# SeptinaryAI_Balldi__elec_driver__driver_.net
KiCad netlist of a schematic drawn in Altium Designer
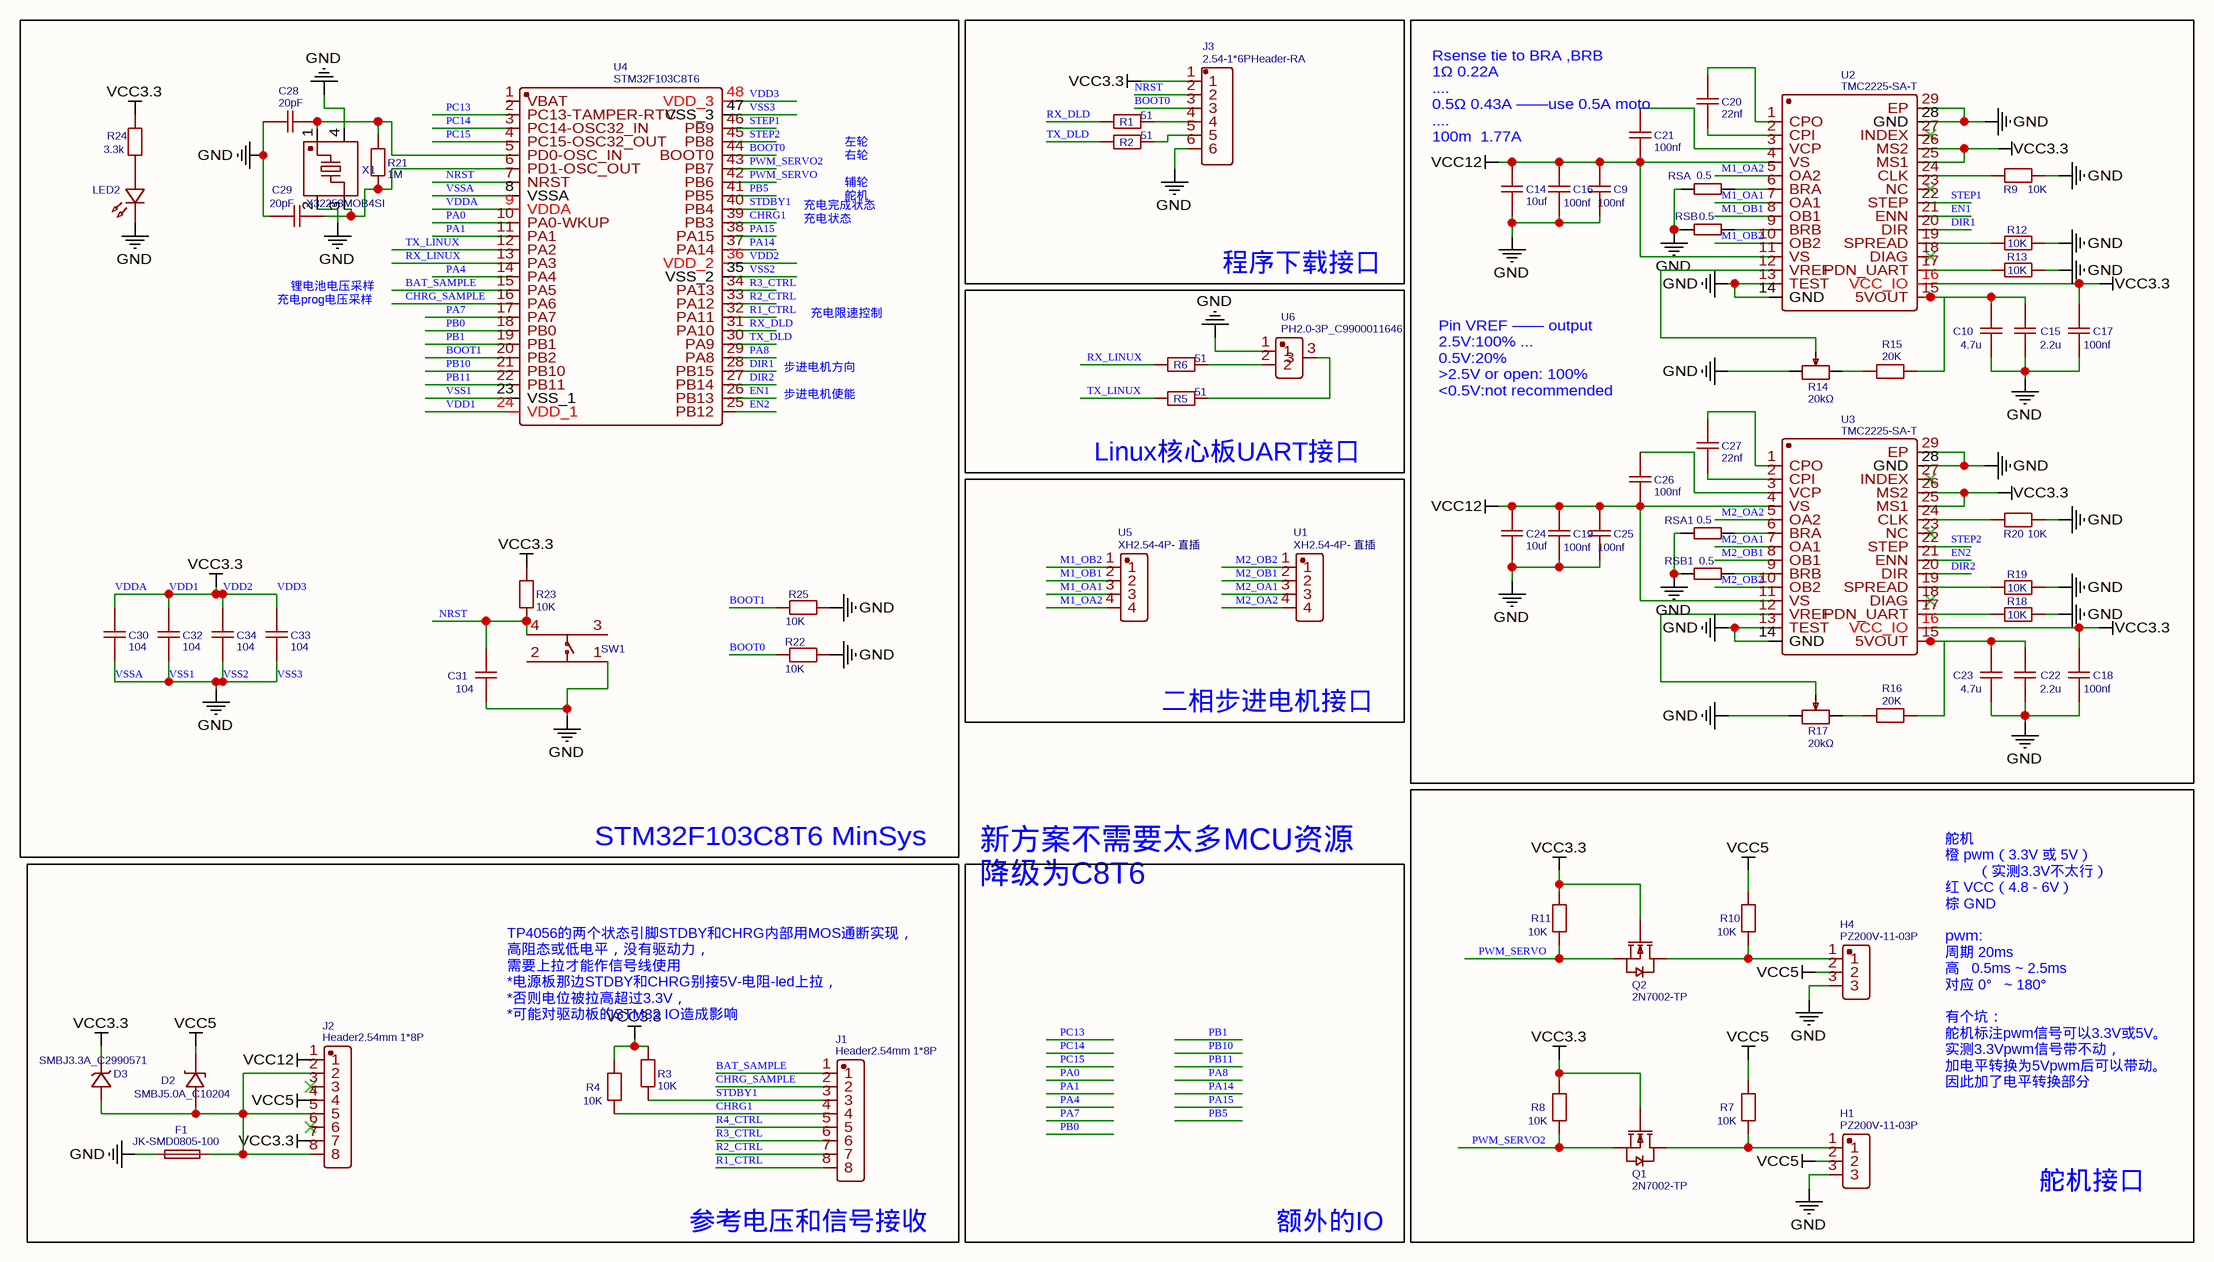
[diagram p0: SeptinaryAI_Balldi__elec_driver__driver_2023-07-21.schdoc]

(export (version "E")
  (design (tool "Eeschema 10.0.6"))
  (components
    (comp (ref "C9")
      (value "100nf")
      (fields (field (name "CONTRIBUTOR") "LCEDA_Lib"))
      (libsource (lib "altium-import") (part "root_1_100nf_"))
    )
    (comp (ref "C10")
      (value "4.7u")
      (fields (field (name "CONTRIBUTOR") "LCSC"))
      (libsource (lib "altium-import") (part "root_1_4.7u_"))
    )
    (comp (ref "C14")
      (value "10uf")
      (fields (field (name "CONTRIBUTOR") "LCEDA_Lib"))
      (libsource (lib "altium-import") (part "root_1_10uf_"))
    )
    (comp (ref "C15")
      (value "2.2u")
      (fields (field (name "CONTRIBUTOR") "LCSC"))
      (libsource (lib "altium-import") (part "root_1_2.2u_"))
    )
    (comp (ref "C16")
      (value "100nf")
      (fields (field (name "CONTRIBUTOR") "LCEDA_Lib"))
      (libsource (lib "altium-import") (part "root_1_100nf_"))
    )
    (comp (ref "C17")
      (value "100nf")
      (fields (field (name "CONTRIBUTOR") "LCEDA_Lib"))
      (libsource (lib "altium-import") (part "root_1_100nf_"))
    )
    (comp (ref "C18")
      (value "100nf")
      (fields (field (name "CONTRIBUTOR") "LCEDA_Lib"))
      (libsource (lib "altium-import") (part "root_1_100nf_"))
    )
    (comp (ref "C19")
      (value "100nf")
      (fields (field (name "CONTRIBUTOR") "LCEDA_Lib"))
      (libsource (lib "altium-import") (part "root_1_100nf_"))
    )
    (comp (ref "C20")
      (value "22nf")
      (fields (field (name "CONTRIBUTOR") "LCEDA_Lib"))
      (libsource (lib "altium-import") (part "root_1_22nf_"))
    )
    (comp (ref "C21")
      (value "100nf")
      (fields (field (name "CONTRIBUTOR") "LCEDA_Lib"))
      (libsource (lib "altium-import") (part "root_1_100nf_"))
    )
    (comp (ref "C22")
      (value "2.2u")
      (fields (field (name "CONTRIBUTOR") "LCSC"))
      (libsource (lib "altium-import") (part "root_1_2.2u_"))
    )
    (comp (ref "C23")
      (value "4.7u")
      (fields (field (name "CONTRIBUTOR") "LCSC"))
      (libsource (lib "altium-import") (part "root_1_4.7u_"))
    )
    (comp (ref "C24")
      (value "10uf")
      (fields (field (name "CONTRIBUTOR") "LCEDA_Lib"))
      (libsource (lib "altium-import") (part "root_1_10uf_"))
    )
    (comp (ref "C25")
      (value "100nf")
      (fields (field (name "CONTRIBUTOR") "LCEDA_Lib"))
      (libsource (lib "altium-import") (part "root_1_100nf_"))
    )
    (comp (ref "C26")
      (value "100nf")
      (fields (field (name "CONTRIBUTOR") "LCEDA_Lib"))
      (libsource (lib "altium-import") (part "root_1_100nf_"))
    )
    (comp (ref "C27")
      (value "22nf")
      (fields (field (name "CONTRIBUTOR") "LCEDA_Lib"))
      (libsource (lib "altium-import") (part "root_1_22nf_"))
    )
    (comp (ref "C28")
      (value "20pF")
      (fields (field (name "CONTRIBUTOR") "LCSC"))
      (libsource (lib "altium-import") (part "root_2_20pF_"))
    )
    (comp (ref "C29")
      (value "20pF")
      (fields (field (name "CONTRIBUTOR") "LCSC"))
      (libsource (lib "altium-import") (part "root_2_20pF_"))
    )
    (comp (ref "C30")
      (value "104")
      (fields (field (name "CONTRIBUTOR") "LCSC"))
      (libsource (lib "altium-import") (part "root_1_104_"))
    )
    (comp (ref "C31")
      (value "104")
      (fields (field (name "CONTRIBUTOR") "LCSC"))
      (libsource (lib "altium-import") (part "root_1_104_"))
    )
    (comp (ref "C32")
      (value "104")
      (fields (field (name "CONTRIBUTOR") "LCSC"))
      (libsource (lib "altium-import") (part "root_1_104_"))
    )
    (comp (ref "C33")
      (value "104")
      (fields (field (name "CONTRIBUTOR") "LCSC"))
      (libsource (lib "altium-import") (part "root_1_104_"))
    )
    (comp (ref "C34")
      (value "104")
      (fields (field (name "CONTRIBUTOR") "LCSC"))
      (libsource (lib "altium-import") (part "root_1_104_"))
    )
    (comp (ref "D2")
      (value "SMBJ5.0A_C10204")
      (libsource (lib "altium-import") (part "root_3_SMBJ5.0A_C10204_"))
    )
    (comp (ref "D3")
      (value "SMBJ3.3A_C2990571")
      (fields
        (field (name "BOM_SUPPLIER PART") "C2990571")
        (field (name "BOM_MANUFACTURER PART") "SMBJ3.3A")
        (field (name "CONTRIBUTOR") "lcsc")
      )
      (libsource (lib "altium-import") (part "root_3_SMBJ3.3A_C2990571_"))
    )
    (comp (ref "F1")
      (value "JK-SMD0805-100")
      (fields (field (name "CONTRIBUTOR") "LCSC"))
      (libsource (lib "altium-import") (part "root_0_JK-SMD0805-100_"))
    )
    (comp (ref "H1")
      (value "PZ200V-11-03P")
      (fields (field (name "CONTRIBUTOR") "LCSC"))
      (libsource (lib "altium-import") (part "root_0_PZ200V-11-03P_"))
    )
    (comp (ref "H4")
      (value "PZ200V-11-03P")
      (fields (field (name "CONTRIBUTOR") "LCSC"))
      (libsource (lib "altium-import") (part "root_0_PZ200V-11-03P_"))
    )
    (comp (ref "J1")
      (value "Header2.54mm 1*8P")
      (libsource (lib "altium-import") (part "root_0_Header2.54mm 1*8P_"))
    )
    (comp (ref "J2")
      (value "Header2.54mm 1*8P")
      (libsource (lib "altium-import") (part "root_0_Header2.54mm 1*8P_"))
    )
    (comp (ref "J3")
      (value "2.54-1*6PHeader-RA")
      (libsource (lib "altium-import") (part "root_0_2.54-1*6PHeader-RA_"))
    )
    (comp (ref "LED2")
      (value "LC191TBCT")
      (fields (field (name "CONTRIBUTOR") "LCSC"))
      (libsource (lib "altium-import") (part "root_1_LC191TBCT_"))
    )
    (comp (ref "Q1")
      (value "2N7002-TP")
      (fields (field (name "CONTRIBUTOR") "LCSC"))
      (libsource (lib "altium-import") (part "root_3_2N7002-TP_"))
    )
    (comp (ref "Q2")
      (value "2N7002-TP")
      (fields (field (name "CONTRIBUTOR") "LCSC"))
      (libsource (lib "altium-import") (part "root_3_2N7002-TP_"))
    )
    (comp (ref "R1")
      (value "51")
      (fields (field (name "CONTRIBUTOR") "LCSC"))
      (libsource (lib "altium-import") (part "root_0_51_"))
    )
    (comp (ref "R2")
      (value "51")
      (fields (field (name "CONTRIBUTOR") "LCSC"))
      (libsource (lib "altium-import") (part "root_0_51_"))
    )
    (comp (ref "R3")
      (value "10K")
      (fields (field (name "CONTRIBUTOR") "LCSC"))
      (libsource (lib "altium-import") (part "root_3_10K_"))
    )
    (comp (ref "R4")
      (value "10K")
      (fields (field (name "CONTRIBUTOR") "LCSC"))
      (libsource (lib "altium-import") (part "root_3_10K_"))
    )
    (comp (ref "R5")
      (value "51")
      (fields (field (name "CONTRIBUTOR") "LCSC"))
      (libsource (lib "altium-import") (part "root_0_51_"))
    )
    (comp (ref "R6")
      (value "51")
      (fields (field (name "CONTRIBUTOR") "LCSC"))
      (libsource (lib "altium-import") (part "root_0_51_"))
    )
    (comp (ref "R7")
      (value "10K")
      (fields (field (name "CONTRIBUTOR") "LCSC"))
      (libsource (lib "altium-import") (part "root_3_10K_"))
    )
    (comp (ref "R8")
      (value "10K")
      (fields (field (name "CONTRIBUTOR") "LCSC"))
      (libsource (lib "altium-import") (part "root_3_10K_"))
    )
    (comp (ref "R9")
      (value "10K")
      (fields (field (name "CONTRIBUTOR") "LCSC"))
      (libsource (lib "altium-import") (part "root_0_10K_"))
    )
    (comp (ref "R10")
      (value "10K")
      (fields (field (name "CONTRIBUTOR") "LCSC"))
      (libsource (lib "altium-import") (part "root_3_10K_"))
    )
    (comp (ref "R11")
      (value "10K")
      (fields (field (name "CONTRIBUTOR") "LCSC"))
      (libsource (lib "altium-import") (part "root_3_10K_"))
    )
    (comp (ref "R12")
      (value "10K")
      (fields (field (name "CONTRIBUTOR") "LCSC"))
      (libsource (lib "altium-import") (part "root_0_10K_"))
    )
    (comp (ref "R13")
      (value "10K")
      (fields (field (name "CONTRIBUTOR") "LCSC"))
      (libsource (lib "altium-import") (part "root_0_10K_"))
    )
    (comp (ref "R14")
      (value "20kΩ")
      (fields
        (field (name "BOM_MANUFACTURER PART") "EVM3ESX50B24")
        (field (name "BOM_SUPPLIER PART") "C11957")
      )
      (libsource (lib "altium-import") (part "root_3_20kΩ_"))
    )
    (comp (ref "R15")
      (value "20K")
      (fields (field (name "CONTRIBUTOR") "LCSC"))
      (libsource (lib "altium-import") (part "root_0_20K_"))
    )
    (comp (ref "R16")
      (value "20K")
      (fields (field (name "CONTRIBUTOR") "LCSC"))
      (libsource (lib "altium-import") (part "root_0_20K_"))
    )
    (comp (ref "R17")
      (value "20kΩ")
      (fields
        (field (name "BOM_MANUFACTURER PART") "EVM3ESX50B24")
        (field (name "BOM_SUPPLIER PART") "C11957")
      )
      (libsource (lib "altium-import") (part "root_3_20kΩ_"))
    )
    (comp (ref "R18")
      (value "10K")
      (fields (field (name "CONTRIBUTOR") "LCSC"))
      (libsource (lib "altium-import") (part "root_0_10K_"))
    )
    (comp (ref "R19")
      (value "10K")
      (fields (field (name "CONTRIBUTOR") "LCSC"))
      (libsource (lib "altium-import") (part "root_0_10K_"))
    )
    (comp (ref "R20")
      (value "10K")
      (fields (field (name "CONTRIBUTOR") "LCSC"))
      (libsource (lib "altium-import") (part "root_0_10K_"))
    )
    (comp (ref "R21")
      (value "1M")
      (fields (field (name "CONTRIBUTOR") "LCSC"))
      (libsource (lib "altium-import") (part "root_3_1M_"))
    )
    (comp (ref "R22")
      (value "10K")
      (fields (field (name "CONTRIBUTOR") "LCSC"))
      (libsource (lib "altium-import") (part "root_2_10K_"))
    )
    (comp (ref "R23")
      (value "10K")
      (fields (field (name "CONTRIBUTOR") "LCSC"))
      (libsource (lib "altium-import") (part "root_1_10K_"))
    )
    (comp (ref "R24")
      (value "3.3k")
      (fields (field (name "CONTRIBUTOR") "LCSC"))
      (libsource (lib "altium-import") (part "root_1_3.3k_"))
    )
    (comp (ref "R25")
      (value "10K")
      (fields (field (name "CONTRIBUTOR") "LCSC"))
      (libsource (lib "altium-import") (part "root_2_10K_"))
    )
    (comp (ref "RSA") (value "0.5") (libsource (lib "altium-import") (part "root_0_0.5_")))
    (comp (ref "RSA1") (value "0.5") (libsource (lib "altium-import") (part "root_0_0.5_")))
    (comp (ref "RSB") (value "0.5") (libsource (lib "altium-import") (part "root_0_0.5_")))
    (comp (ref "RSB1") (value "0.5") (libsource (lib "altium-import") (part "root_0_0.5_")))
    (comp (ref "SW1")
      (value "K2-1109SP-A4SA")
      (libsource (lib "altium-import") (part "root_0_K2-1109SP-A4SA_"))
    )
    (comp (ref "U1")
      (value "XH2.54-4P- 直插")
      (fields (field (name "BOM_SUPPLIER PART") "C9900000103") (field (name "CONTRIBUTOR") "LCSC"))
      (libsource (lib "altium-import") (part "root_0_XH2.54-4P- 直插_"))
    )
    (comp (ref "U2")
      (value "TMC2225-SA-T")
      (fields (field (name "BOM_SUPPLIER PART") "C516358") (field (name "CONTRIBUTOR") "LCSC"))
      (libsource (lib "altium-import") (part "root_0_TMC2225-SA-T_"))
    )
    (comp (ref "U3")
      (value "TMC2225-SA-T")
      (fields (field (name "BOM_SUPPLIER PART") "C516358") (field (name "CONTRIBUTOR") "LCSC"))
      (libsource (lib "altium-import") (part "root_0_TMC2225-SA-T_"))
    )
    (comp (ref "U4")
      (value "STM32F103C8T6")
      (fields (field (name "BOM_SUPPLIER PART") "C8734"))
      (libsource (lib "altium-import") (part "root_0_STM32F103C8T6_"))
    )
    (comp (ref "U5")
      (value "XH2.54-4P- 直插")
      (fields (field (name "BOM_SUPPLIER PART") "C9900000103") (field (name "CONTRIBUTOR") "LCSC"))
      (libsource (lib "altium-import") (part "root_0_XH2.54-4P- 直插_"))
    )
    (comp (ref "U6")
      (value "PH2.0-3P_C9900011646")
      (fields
        (field (name "BOM_SUPPLIER PART") "C9900011646")
        (field (name "BOM_MANUFACTURER PART") "PH2.0-3P")
        (field (name "CONTRIBUTOR") "LCSC")
      )
      (libsource (lib "altium-import") (part "root_0_PH2.0-3P_C9900011646_"))
    )
    (comp (ref "X1")
      (value "X32258MOB4SI")
      (fields (field (name "CONTRIBUTOR") "LCSC"))
      (libsource (lib "altium-import") (part "root_3_X32258MOB4SI_"))
    )
  )
  (nets
    (net (code "1") (name "/BAT_SAMPLE") (class "Default")
      (node (ref "J1") (pin "1") (pinfunction "1_1") (pintype "passive"))
      (node (ref "U4") (pin "15") (pinfunction "PA5_15") (pintype "passive"))
    )
    (net (code "2") (name "/BOOT0") (class "Default")
      (node (ref "J3") (pin "3") (pinfunction "3_3") (pintype "passive"))
      (node (ref "R22") (pin "2") (pinfunction "2_2") (pintype "passive"))
      (node (ref "U4") (pin "44") (pinfunction "BOOT0_44") (pintype "passive"))
    )
    (net (code "3") (name "/BOOT1") (class "Default")
      (node (ref "R25") (pin "2") (pinfunction "2_2") (pintype "passive"))
      (node (ref "U4") (pin "20") (pinfunction "PB2_20") (pintype "passive"))
    )
    (net (code "4") (name "/CHRG1") (class "Default")
      (node (ref "J1") (pin "4") (pinfunction "4_4") (pintype "passive"))
      (node (ref "R4") (pin "2") (pinfunction "2_2") (pintype "passive"))
      (node (ref "U4") (pin "39") (pinfunction "PB3_39") (pintype "passive"))
    )
    (net (code "5") (name "/CHRG_SAMPLE") (class "Default")
      (node (ref "J1") (pin "2") (pinfunction "2_2") (pintype "passive"))
      (node (ref "U4") (pin "16") (pinfunction "PA6_16") (pintype "passive"))
    )
    (net (code "6") (name "/DIR1") (class "Default")
      (node (ref "U2") (pin "20") (pinfunction "DIR_20") (pintype "passive"))
      (node (ref "U4") (pin "28") (pinfunction "PB15_28") (pintype "passive"))
    )
    (net (code "7") (name "/DIR2") (class "Default")
      (node (ref "U3") (pin "20") (pinfunction "DIR_20") (pintype "passive"))
      (node (ref "U4") (pin "27") (pinfunction "PB14_27") (pintype "passive"))
    )
    (net (code "8") (name "/EN1") (class "Default")
      (node (ref "U2") (pin "21") (pinfunction "ENN_21") (pintype "passive"))
      (node (ref "U4") (pin "26") (pinfunction "PB13_26") (pintype "passive"))
    )
    (net (code "9") (name "/EN2") (class "Default")
      (node (ref "U3") (pin "21") (pinfunction "ENN_21") (pintype "passive"))
      (node (ref "U4") (pin "25") (pinfunction "PB12_25") (pintype "passive"))
    )
    (net (code "10") (name "/M1_OA1") (class "Default")
      (node (ref "U2") (pin "7") (pinfunction "OA1_7") (pintype "passive"))
      (node (ref "U5") (pin "3") (pinfunction "3_3") (pintype "passive"))
    )
    (net (code "11") (name "/M1_OA2") (class "Default")
      (node (ref "U2") (pin "5") (pinfunction "OA2_5") (pintype "passive"))
      (node (ref "U5") (pin "4") (pinfunction "4_4") (pintype "passive"))
    )
    (net (code "12") (name "/M1_OB1") (class "Default")
      (node (ref "U2") (pin "8") (pinfunction "OB1_8") (pintype "passive"))
      (node (ref "U5") (pin "2") (pinfunction "2_2") (pintype "passive"))
    )
    (net (code "13") (name "/M1_OB2") (class "Default")
      (node (ref "U2") (pin "10") (pinfunction "OB2_10") (pintype "passive"))
      (node (ref "U5") (pin "1") (pinfunction "1_1") (pintype "passive"))
    )
    (net (code "14") (name "/M2_OA1") (class "Default")
      (node (ref "U1") (pin "3") (pinfunction "3_3") (pintype "passive"))
      (node (ref "U3") (pin "7") (pinfunction "OA1_7") (pintype "passive"))
    )
    (net (code "15") (name "/M2_OA2") (class "Default")
      (node (ref "U1") (pin "4") (pinfunction "4_4") (pintype "passive"))
      (node (ref "U3") (pin "5") (pinfunction "OA2_5") (pintype "passive"))
    )
    (net (code "16") (name "/M2_OB1") (class "Default")
      (node (ref "U1") (pin "2") (pinfunction "2_2") (pintype "passive"))
      (node (ref "U3") (pin "8") (pinfunction "OB1_8") (pintype "passive"))
    )
    (net (code "17") (name "/M2_OB2") (class "Default")
      (node (ref "U1") (pin "1") (pinfunction "1_1") (pintype "passive"))
      (node (ref "U3") (pin "10") (pinfunction "OB2_10") (pintype "passive"))
    )
    (net (code "18") (name "/NRST") (class "Default")
      (node (ref "C31") (pin "2") (pinfunction "2_2") (pintype "passive"))
      (node (ref "J3") (pin "2") (pinfunction "2_2") (pintype "passive"))
      (node (ref "R23") (pin "1") (pinfunction "1_1") (pintype "passive"))
      (node (ref "SW1") (pin "4") (pinfunction "4_4") (pintype "passive"))
      (node (ref "U4") (pin "7") (pinfunction "NRST_7") (pintype "passive"))
    )
    (net (code "19") (name "/PA0") (class "Default")
      (node (ref "U4") (pin "10") (pinfunction "PA0-WKUP_10") (pintype "passive"))
    )
    (net (code "20") (name "/PA1") (class "Default")
      (node (ref "U4") (pin "11") (pinfunction "PA1_11") (pintype "passive"))
    )
    (net (code "21") (name "/PA4") (class "Default")
      (node (ref "U4") (pin "14") (pinfunction "PA4_14") (pintype "passive"))
    )
    (net (code "22") (name "/PA7") (class "Default")
      (node (ref "U4") (pin "17") (pinfunction "PA7_17") (pintype "passive"))
    )
    (net (code "23") (name "/PA8") (class "Default")
      (node (ref "U4") (pin "29") (pinfunction "PA8_29") (pintype "passive"))
    )
    (net (code "24") (name "/PA14") (class "Default")
      (node (ref "U4") (pin "37") (pinfunction "PA14_37") (pintype "passive"))
    )
    (net (code "25") (name "/PA15") (class "Default")
      (node (ref "U4") (pin "38") (pinfunction "PA15_38") (pintype "passive"))
    )
    (net (code "26") (name "/PB0") (class "Default")
      (node (ref "U4") (pin "18") (pinfunction "PB0_18") (pintype "passive"))
    )
    (net (code "27") (name "/PB1") (class "Default")
      (node (ref "U4") (pin "19") (pinfunction "PB1_19") (pintype "passive"))
    )
    (net (code "28") (name "/PB5") (class "Default")
      (node (ref "U4") (pin "41") (pinfunction "PB5_41") (pintype "passive"))
    )
    (net (code "29") (name "/PB10") (class "Default")
      (node (ref "U4") (pin "21") (pinfunction "PB10_21") (pintype "passive"))
    )
    (net (code "30") (name "/PB11") (class "Default")
      (node (ref "U4") (pin "22") (pinfunction "PB11_22") (pintype "passive"))
    )
    (net (code "31") (name "/PC13") (class "Default")
      (node (ref "U4") (pin "2") (pinfunction "PC13-TAMPER-RTC_2") (pintype "passive"))
    )
    (net (code "32") (name "/PC14") (class "Default")
      (node (ref "U4") (pin "3") (pinfunction "PC14-OSC32_IN_3") (pintype "passive"))
    )
    (net (code "33") (name "/PC15") (class "Default")
      (node (ref "U4") (pin "4") (pinfunction "PC15-OSC32_OUT_4") (pintype "passive"))
    )
    (net (code "34") (name "/PWM_SERVO") (class "Default")
      (node (ref "Q2") (pin "2") (pinfunction "S_2") (pintype "passive"))
      (node (ref "R11") (pin "2") (pinfunction "2_2") (pintype "passive"))
      (node (ref "U4") (pin "42") (pinfunction "PB6_42") (pintype "passive"))
    )
    (net (code "35") (name "/PWM_SERVO2") (class "Default")
      (node (ref "Q1") (pin "2") (pinfunction "S_2") (pintype "passive"))
      (node (ref "R8") (pin "2") (pinfunction "2_2") (pintype "passive"))
      (node (ref "U4") (pin "43") (pinfunction "PB7_43") (pintype "passive"))
    )
    (net (code "36") (name "/R1_CTRL") (class "Default")
      (node (ref "J1") (pin "8") (pinfunction "8_8") (pintype "passive"))
      (node (ref "U4") (pin "32") (pinfunction "PA11_32") (pintype "passive"))
    )
    (net (code "37") (name "/R2_CTRL") (class "Default")
      (node (ref "J1") (pin "7") (pinfunction "7_7") (pintype "passive"))
      (node (ref "U4") (pin "33") (pinfunction "PA12_33") (pintype "passive"))
    )
    (net (code "38") (name "/R3_CTRL") (class "Default")
      (node (ref "J1") (pin "6") (pinfunction "6_6") (pintype "passive"))
      (node (ref "U4") (pin "34") (pinfunction "PA13_34") (pintype "passive"))
    )
    (net (code "39") (name "/R4_CTRL") (class "Default")
      (node (ref "J1") (pin "5") (pinfunction "5_5") (pintype "passive"))
    )
    (net (code "40") (name "/RX_DLD") (class "Default")
      (node (ref "R1") (pin "1") (pinfunction "1_1") (pintype "passive"))
      (node (ref "U4") (pin "31") (pinfunction "PA10_31") (pintype "passive"))
    )
    (net (code "41") (name "/RX_LINUX") (class "Default")
      (node (ref "R6") (pin "1") (pinfunction "1_1") (pintype "passive"))
      (node (ref "U4") (pin "13") (pinfunction "PA3_13") (pintype "passive"))
    )
    (net (code "42") (name "/STDBY1") (class "Default")
      (node (ref "J1") (pin "3") (pinfunction "3_3") (pintype "passive"))
      (node (ref "R3") (pin "2") (pinfunction "2_2") (pintype "passive"))
      (node (ref "U4") (pin "40") (pinfunction "PB4_40") (pintype "passive"))
    )
    (net (code "43") (name "/STEP1") (class "Default")
      (node (ref "U2") (pin "22") (pinfunction "STEP_22") (pintype "passive"))
      (node (ref "U4") (pin "46") (pinfunction "PB9_46") (pintype "passive"))
    )
    (net (code "44") (name "/STEP2") (class "Default")
      (node (ref "U3") (pin "22") (pinfunction "STEP_22") (pintype "passive"))
      (node (ref "U4") (pin "45") (pinfunction "PB8_45") (pintype "passive"))
    )
    (net (code "45") (name "/TX_DLD") (class "Default")
      (node (ref "R2") (pin "1") (pinfunction "1_1") (pintype "passive"))
      (node (ref "U4") (pin "30") (pinfunction "PA9_30") (pintype "passive"))
    )
    (net (code "46") (name "/TX_LINUX") (class "Default")
      (node (ref "R5") (pin "1") (pinfunction "1_1") (pintype "passive"))
      (node (ref "U4") (pin "12") (pinfunction "PA2_12") (pintype "passive"))
    )
    (net (code "47") (name "GND") (class "Default")
      (node (ref "C10") (pin "1") (pinfunction "1_1") (pintype "passive"))
      (node (ref "C14") (pin "1") (pinfunction "1_1") (pintype "passive"))
      (node (ref "C15") (pin "1") (pinfunction "1_1") (pintype "passive"))
      (node (ref "C16") (pin "1") (pinfunction "1_1") (pintype "passive"))
      (node (ref "C17") (pin "1") (pinfunction "1_1") (pintype "passive"))
      (node (ref "C18") (pin "1") (pinfunction "1_1") (pintype "passive"))
      (node (ref "C19") (pin "1") (pinfunction "1_1") (pintype "passive"))
      (node (ref "C22") (pin "1") (pinfunction "1_1") (pintype "passive"))
      (node (ref "C23") (pin "1") (pinfunction "1_1") (pintype "passive"))
      (node (ref "C24") (pin "1") (pinfunction "1_1") (pintype "passive"))
      (node (ref "C25") (pin "1") (pinfunction "1_1") (pintype "passive"))
      (node (ref "C28") (pin "2") (pinfunction "2_2") (pintype "passive"))
      (node (ref "C29") (pin "2") (pinfunction "2_2") (pintype "passive"))
      (node (ref "C30") (pin "1") (pinfunction "1_1") (pintype "passive"))
      (node (ref "C31") (pin "1") (pinfunction "1_1") (pintype "passive"))
      (node (ref "C32") (pin "1") (pinfunction "1_1") (pintype "passive"))
      (node (ref "C33") (pin "1") (pinfunction "1_1") (pintype "passive"))
      (node (ref "C34") (pin "1") (pinfunction "1_1") (pintype "passive"))
      (node (ref "C9") (pin "1") (pinfunction "1_1") (pintype "passive"))
      (node (ref "F1") (pin "1") (pinfunction "1_1") (pintype "passive"))
      (node (ref "H1") (pin "3") (pinfunction "3_3") (pintype "passive"))
      (node (ref "H4") (pin "3") (pinfunction "3_3") (pintype "passive"))
      (node (ref "J3") (pin "6") (pinfunction "6_6") (pintype "passive"))
      (node (ref "LED2") (pin "1") (pinfunction "K_1") (pintype "passive"))
      (node (ref "R12") (pin "2") (pinfunction "2_2") (pintype "passive"))
      (node (ref "R13") (pin "2") (pinfunction "2_2") (pintype "passive"))
      (node (ref "R14") (pin "3") (pinfunction "3_3") (pintype "passive"))
      (node (ref "R17") (pin "3") (pinfunction "3_3") (pintype "passive"))
      (node (ref "R18") (pin "2") (pinfunction "2_2") (pintype "passive"))
      (node (ref "R19") (pin "2") (pinfunction "2_2") (pintype "passive"))
      (node (ref "R20") (pin "2") (pinfunction "2_2") (pintype "passive"))
      (node (ref "R22") (pin "1") (pinfunction "1_1") (pintype "passive"))
      (node (ref "R25") (pin "1") (pinfunction "1_1") (pintype "passive"))
      (node (ref "R9") (pin "2") (pinfunction "2_2") (pintype "passive"))
      (node (ref "RSA") (pin "1") (pinfunction "1_1") (pintype "passive"))
      (node (ref "RSA1") (pin "1") (pinfunction "1_1") (pintype "passive"))
      (node (ref "RSB") (pin "1") (pinfunction "1_1") (pintype "passive"))
      (node (ref "RSB1") (pin "1") (pinfunction "1_1") (pintype "passive"))
      (node (ref "SW1") (pin "1") (pinfunction "1_1") (pintype "passive"))
      (node (ref "U2") (pin "13") (pinfunction "TEST_13") (pintype "passive"))
      (node (ref "U2") (pin "14") (pinfunction "GND_14") (pintype "passive"))
      (node (ref "U2") (pin "28") (pinfunction "GND_28") (pintype "passive"))
      (node (ref "U2") (pin "29") (pinfunction "EP_29") (pintype "passive"))
      (node (ref "U3") (pin "13") (pinfunction "TEST_13") (pintype "passive"))
      (node (ref "U3") (pin "14") (pinfunction "GND_14") (pintype "passive"))
      (node (ref "U3") (pin "28") (pinfunction "GND_28") (pintype "passive"))
      (node (ref "U3") (pin "29") (pinfunction "EP_29") (pintype "passive"))
      (node (ref "U4") (pin "23") (pinfunction "VSS_1_23") (pintype "passive"))
      (node (ref "U4") (pin "35") (pinfunction "VSS_2_35") (pintype "passive"))
      (node (ref "U4") (pin "47") (pinfunction "VSS_3_47") (pintype "passive"))
      (node (ref "U4") (pin "8") (pinfunction "VSSA_8") (pintype "passive"))
      (node (ref "U6") (pin "1") (pinfunction "1_1") (pintype "passive"))
      (node (ref "X1") (pin "2") (pinfunction "GND_2") (pintype "passive"))
      (node (ref "X1") (pin "4") (pinfunction "GND_4") (pintype "passive"))
    )
    (net (code "48") (name "Net-(D2-A)") (class "Default")
      (node (ref "D2") (pin "1") (pinfunction "A_1") (pintype "passive"))
      (node (ref "D3") (pin "1") (pinfunction "A_1") (pintype "passive"))
      (node (ref "F1") (pin "2") (pinfunction "2_2") (pintype "passive"))
      (node (ref "J2") (pin "2") (pinfunction "2_2") (pintype "passive"))
      (node (ref "J2") (pin "5") (pinfunction "5_5") (pintype "passive"))
      (node (ref "J2") (pin "8") (pinfunction "8_8") (pintype "passive"))
    )
    (net (code "49") (name "Net-(J3-Pad4)") (class "Default")
      (node (ref "J3") (pin "4") (pinfunction "4_4") (pintype "passive"))
      (node (ref "R1") (pin "2") (pinfunction "2_2") (pintype "passive"))
    )
    (net (code "50") (name "Net-(J3-Pad5)") (class "Default")
      (node (ref "J3") (pin "5") (pinfunction "5_5") (pintype "passive"))
      (node (ref "R2") (pin "2") (pinfunction "2_2") (pintype "passive"))
    )
    (net (code "51") (name "Net-(LED2-A)") (class "Default")
      (node (ref "LED2") (pin "2") (pinfunction "A_2") (pintype "passive"))
      (node (ref "R24") (pin "1") (pinfunction "1_1") (pintype "passive"))
    )
    (net (code "52") (name "Net-(Q1-D)") (class "Default")
      (node (ref "H1") (pin "1") (pinfunction "1_1") (pintype "passive"))
      (node (ref "Q1") (pin "3") (pinfunction "D_3") (pintype "passive"))
      (node (ref "R7") (pin "2") (pinfunction "2_2") (pintype "passive"))
    )
    (net (code "53") (name "Net-(Q2-D)") (class "Default")
      (node (ref "H4") (pin "1") (pinfunction "1_1") (pintype "passive"))
      (node (ref "Q2") (pin "3") (pinfunction "D_3") (pintype "passive"))
      (node (ref "R10") (pin "2") (pinfunction "2_2") (pintype "passive"))
    )
    (net (code "54") (name "Net-(R5-Pad2)") (class "Default")
      (node (ref "R5") (pin "2") (pinfunction "2_2") (pintype "passive"))
      (node (ref "U6") (pin "3") (pinfunction "3_3") (pintype "passive"))
    )
    (net (code "55") (name "Net-(R6-Pad2)") (class "Default")
      (node (ref "R6") (pin "2") (pinfunction "2_2") (pintype "passive"))
      (node (ref "U6") (pin "2") (pinfunction "2_2") (pintype "passive"))
    )
    (net (code "56") (name "Net-(R14-Pad1)") (class "Default")
      (node (ref "R14") (pin "1") (pinfunction "1_1") (pintype "passive"))
      (node (ref "R15") (pin "1") (pinfunction "1_1") (pintype "passive"))
    )
    (net (code "57") (name "Net-(R16-Pad1)") (class "Default")
      (node (ref "R16") (pin "1") (pinfunction "1_1") (pintype "passive"))
      (node (ref "R17") (pin "1") (pinfunction "1_1") (pintype "passive"))
    )
    (net (code "58") (name "Net-(U2-5VOUT)") (class "Default")
      (node (ref "C10") (pin "2") (pinfunction "2_2") (pintype "passive"))
      (node (ref "C15") (pin "2") (pinfunction "2_2") (pintype "passive"))
      (node (ref "R15") (pin "2") (pinfunction "2_2") (pintype "passive"))
      (node (ref "U2") (pin "15") (pinfunction "5VOUT_15") (pintype "passive"))
    )
    (net (code "59") (name "Net-(U2-BRA)") (class "Default")
      (node (ref "RSA") (pin "2") (pinfunction "2_2") (pintype "passive"))
      (node (ref "U2") (pin "6") (pinfunction "BRA_6") (pintype "passive"))
    )
    (net (code "60") (name "Net-(U2-BRB)") (class "Default")
      (node (ref "RSB") (pin "2") (pinfunction "2_2") (pintype "passive"))
      (node (ref "U2") (pin "9") (pinfunction "BRB_9") (pintype "passive"))
    )
    (net (code "61") (name "Net-(U2-CLK)") (class "Default")
      (node (ref "R9") (pin "1") (pinfunction "1_1") (pintype "passive"))
      (node (ref "U2") (pin "24") (pinfunction "CLK_24") (pintype "passive"))
    )
    (net (code "62") (name "Net-(U2-CPI)") (class "Default")
      (node (ref "C20") (pin "1") (pinfunction "1_1") (pintype "passive"))
      (node (ref "U2") (pin "2") (pinfunction "CPI_2") (pintype "passive"))
    )
    (net (code "63") (name "Net-(U2-CPO)") (class "Default")
      (node (ref "C20") (pin "2") (pinfunction "2_2") (pintype "passive"))
      (node (ref "U2") (pin "1") (pinfunction "CPO_1") (pintype "passive"))
    )
    (net (code "64") (name "Net-(U2-PDN_UART)") (class "Default")
      (node (ref "R13") (pin "1") (pinfunction "1_1") (pintype "passive"))
      (node (ref "U2") (pin "17") (pinfunction "PDN_UART_17") (pintype "passive"))
    )
    (net (code "65") (name "Net-(U2-SPREAD)") (class "Default")
      (node (ref "R12") (pin "1") (pinfunction "1_1") (pintype "passive"))
      (node (ref "U2") (pin "19") (pinfunction "SPREAD_19") (pintype "passive"))
    )
    (net (code "66") (name "Net-(U2-VCP)") (class "Default")
      (node (ref "C21") (pin "2") (pinfunction "2_2") (pintype "passive"))
      (node (ref "U2") (pin "3") (pinfunction "VCP_3") (pintype "passive"))
    )
    (net (code "67") (name "Net-(U2-VREF)") (class "Default")
      (node (ref "R14") (pin "2") (pinfunction "2_2") (pintype "passive"))
      (node (ref "U2") (pin "12") (pinfunction "VREF_12") (pintype "passive"))
    )
    (net (code "68") (name "Net-(U3-5VOUT)") (class "Default")
      (node (ref "C22") (pin "2") (pinfunction "2_2") (pintype "passive"))
      (node (ref "C23") (pin "2") (pinfunction "2_2") (pintype "passive"))
      (node (ref "R16") (pin "2") (pinfunction "2_2") (pintype "passive"))
      (node (ref "U3") (pin "15") (pinfunction "5VOUT_15") (pintype "passive"))
    )
    (net (code "69") (name "Net-(U3-BRA)") (class "Default")
      (node (ref "RSA1") (pin "2") (pinfunction "2_2") (pintype "passive"))
      (node (ref "U3") (pin "6") (pinfunction "BRA_6") (pintype "passive"))
    )
    (net (code "70") (name "Net-(U3-BRB)") (class "Default")
      (node (ref "RSB1") (pin "2") (pinfunction "2_2") (pintype "passive"))
      (node (ref "U3") (pin "9") (pinfunction "BRB_9") (pintype "passive"))
    )
    (net (code "71") (name "Net-(U3-CLK)") (class "Default")
      (node (ref "R20") (pin "1") (pinfunction "1_1") (pintype "passive"))
      (node (ref "U3") (pin "24") (pinfunction "CLK_24") (pintype "passive"))
    )
    (net (code "72") (name "Net-(U3-CPI)") (class "Default")
      (node (ref "C27") (pin "1") (pinfunction "1_1") (pintype "passive"))
      (node (ref "U3") (pin "2") (pinfunction "CPI_2") (pintype "passive"))
    )
    (net (code "73") (name "Net-(U3-CPO)") (class "Default")
      (node (ref "C27") (pin "2") (pinfunction "2_2") (pintype "passive"))
      (node (ref "U3") (pin "1") (pinfunction "CPO_1") (pintype "passive"))
    )
    (net (code "74") (name "Net-(U3-PDN_UART)") (class "Default")
      (node (ref "R18") (pin "1") (pinfunction "1_1") (pintype "passive"))
      (node (ref "U3") (pin "17") (pinfunction "PDN_UART_17") (pintype "passive"))
    )
    (net (code "75") (name "Net-(U3-SPREAD)") (class "Default")
      (node (ref "R19") (pin "1") (pinfunction "1_1") (pintype "passive"))
      (node (ref "U3") (pin "19") (pinfunction "SPREAD_19") (pintype "passive"))
    )
    (net (code "76") (name "Net-(U3-VCP)") (class "Default")
      (node (ref "C26") (pin "2") (pinfunction "2_2") (pintype "passive"))
      (node (ref "U3") (pin "3") (pinfunction "VCP_3") (pintype "passive"))
    )
    (net (code "77") (name "Net-(U3-VREF)") (class "Default")
      (node (ref "R17") (pin "2") (pinfunction "2_2") (pintype "passive"))
      (node (ref "U3") (pin "12") (pinfunction "VREF_12") (pintype "passive"))
    )
    (net (code "78") (name "Net-(U4-PD0-OSC_IN)") (class "Default")
      (node (ref "C28") (pin "1") (pinfunction "1_1") (pintype "passive"))
      (node (ref "R21") (pin "1") (pinfunction "1_1") (pintype "passive"))
      (node (ref "U4") (pin "5") (pinfunction "PD0-OSC_IN_5") (pintype "passive"))
      (node (ref "X1") (pin "1") (pinfunction "1_1") (pintype "passive"))
    )
    (net (code "79") (name "Net-(U4-PD1-OSC_OUT)") (class "Default")
      (node (ref "C29") (pin "1") (pinfunction "1_1") (pintype "passive"))
      (node (ref "R21") (pin "2") (pinfunction "2_2") (pintype "passive"))
      (node (ref "U4") (pin "6") (pinfunction "PD1-OSC_OUT_6") (pintype "passive"))
      (node (ref "X1") (pin "3") (pinfunction "3_3") (pintype "passive"))
    )
    (net (code "80") (name "VCC3.3") (class "Default")
      (node (ref "C17") (pin "2") (pinfunction "2_2") (pintype "passive"))
      (node (ref "C18") (pin "2") (pinfunction "2_2") (pintype "passive"))
      (node (ref "C30") (pin "2") (pinfunction "2_2") (pintype "passive"))
      (node (ref "C32") (pin "2") (pinfunction "2_2") (pintype "passive"))
      (node (ref "C33") (pin "2") (pinfunction "2_2") (pintype "passive"))
      (node (ref "C34") (pin "2") (pinfunction "2_2") (pintype "passive"))
      (node (ref "D3") (pin "2") (pinfunction "C_2") (pintype "passive"))
      (node (ref "J2") (pin "7") (pinfunction "7_7") (pintype "passive"))
      (node (ref "J3") (pin "1") (pinfunction "1_1") (pintype "passive"))
      (node (ref "Q1") (pin "1") (pinfunction "G_1") (pintype "passive"))
      (node (ref "Q2") (pin "1") (pinfunction "G_1") (pintype "passive"))
      (node (ref "R11") (pin "1") (pinfunction "1_1") (pintype "passive"))
      (node (ref "R23") (pin "2") (pinfunction "2_2") (pintype "passive"))
      (node (ref "R24") (pin "2") (pinfunction "2_2") (pintype "passive"))
      (node (ref "R3") (pin "1") (pinfunction "1_1") (pintype "passive"))
      (node (ref "R4") (pin "1") (pinfunction "1_1") (pintype "passive"))
      (node (ref "R8") (pin "1") (pinfunction "1_1") (pintype "passive"))
      (node (ref "U2") (pin "16") (pinfunction "VCC_IO_16") (pintype "passive"))
      (node (ref "U2") (pin "25") (pinfunction "MS1_25") (pintype "passive"))
      (node (ref "U2") (pin "26") (pinfunction "MS2_26") (pintype "passive"))
      (node (ref "U3") (pin "16") (pinfunction "VCC_IO_16") (pintype "passive"))
      (node (ref "U3") (pin "25") (pinfunction "MS1_25") (pintype "passive"))
      (node (ref "U3") (pin "26") (pinfunction "MS2_26") (pintype "passive"))
      (node (ref "U4") (pin "24") (pinfunction "VDD_1_24") (pintype "passive"))
      (node (ref "U4") (pin "36") (pinfunction "VDD_2_36") (pintype "passive"))
      (node (ref "U4") (pin "48") (pinfunction "VDD_3_48") (pintype "passive"))
      (node (ref "U4") (pin "9") (pinfunction "VDDA_9") (pintype "passive"))
    )
    (net (code "81") (name "VCC5") (class "Default")
      (node (ref "D2") (pin "2") (pinfunction "K_2") (pintype "passive"))
      (node (ref "H1") (pin "2") (pinfunction "2_2") (pintype "passive"))
      (node (ref "H4") (pin "2") (pinfunction "2_2") (pintype "passive"))
      (node (ref "J2") (pin "4") (pinfunction "4_4") (pintype "passive"))
      (node (ref "R10") (pin "1") (pinfunction "1_1") (pintype "passive"))
      (node (ref "R7") (pin "1") (pinfunction "1_1") (pintype "passive"))
    )
    (net (code "82") (name "VCC12") (class "Default")
      (node (ref "C14") (pin "2") (pinfunction "2_2") (pintype "passive"))
      (node (ref "C16") (pin "2") (pinfunction "2_2") (pintype "passive"))
      (node (ref "C19") (pin "2") (pinfunction "2_2") (pintype "passive"))
      (node (ref "C21") (pin "1") (pinfunction "1_1") (pintype "passive"))
      (node (ref "C24") (pin "2") (pinfunction "2_2") (pintype "passive"))
      (node (ref "C25") (pin "2") (pinfunction "2_2") (pintype "passive"))
      (node (ref "C26") (pin "1") (pinfunction "1_1") (pintype "passive"))
      (node (ref "C9") (pin "2") (pinfunction "2_2") (pintype "passive"))
      (node (ref "J2") (pin "1") (pinfunction "1_1") (pintype "passive"))
      (node (ref "U2") (pin "11") (pinfunction "VS_11") (pintype "passive"))
      (node (ref "U2") (pin "4") (pinfunction "VS_4") (pintype "passive"))
      (node (ref "U3") (pin "11") (pinfunction "VS_11") (pintype "passive"))
      (node (ref "U3") (pin "4") (pinfunction "VS_4") (pintype "passive"))
    )
    (net (code "83") (name "unconnected-(J2-Pad3)") (class "Default")
      (node (ref "J2") (pin "3") (pinfunction "3_3") (pintype "passive+no_connect"))
    )
    (net (code "84") (name "unconnected-(J2-Pad6)") (class "Default")
      (node (ref "J2") (pin "6") (pinfunction "6_6") (pintype "passive+no_connect"))
    )
    (net (code "85") (name "unconnected-(SW1-Pad2)") (class "Default")
      (node (ref "SW1") (pin "2") (pinfunction "2_2") (pintype "passive"))
    )
    (net (code "86") (name "unconnected-(SW1-Pad3)") (class "Default")
      (node (ref "SW1") (pin "3") (pinfunction "3_3") (pintype "passive"))
    )
    (net (code "87") (name "unconnected-(U2-DIAG-Pad18)") (class "Default")
      (node (ref "U2") (pin "18") (pinfunction "DIAG_18") (pintype "passive+no_connect"))
    )
    (net (code "88") (name "unconnected-(U2-INDEX-Pad27)") (class "Default")
      (node (ref "U2") (pin "27") (pinfunction "INDEX_27") (pintype "passive+no_connect"))
    )
    (net (code "89") (name "unconnected-(U2-NC-Pad23)") (class "Default")
      (node (ref "U2") (pin "23") (pinfunction "NC_23") (pintype "passive+no_connect"))
    )
    (net (code "90") (name "unconnected-(U3-DIAG-Pad18)") (class "Default")
      (node (ref "U3") (pin "18") (pinfunction "DIAG_18") (pintype "passive+no_connect"))
    )
    (net (code "91") (name "unconnected-(U3-INDEX-Pad27)") (class "Default")
      (node (ref "U3") (pin "27") (pinfunction "INDEX_27") (pintype "passive+no_connect"))
    )
    (net (code "92") (name "unconnected-(U3-NC-Pad23)") (class "Default")
      (node (ref "U3") (pin "23") (pinfunction "NC_23") (pintype "passive+no_connect"))
    )
    (net (code "93") (name "unconnected-(U4-VBAT-Pad1)") (class "Default")
      (node (ref "U4") (pin "1") (pinfunction "VBAT_1") (pintype "passive"))
    )
  )
)
